# IRN-back-BNC.net
KiCad netlist of a schematic drawn in Altium Designer
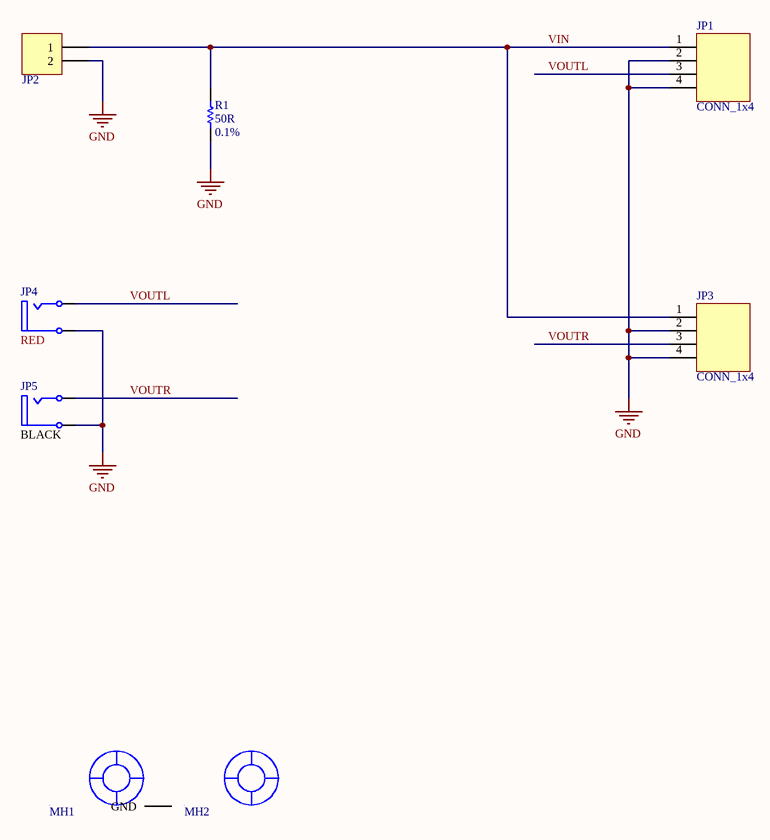
[diagram p0: IRN-back-BNC.SchDoc]

(export (version "E")
  (design (tool "Eeschema 10.0.6"))
  (components
    (comp (ref "JP1")
      (value "CONN_1x4")
      (footprint "CONN_HDR1X4-No3D")
      (description "Header, 4-Pin")
      (fields (field (name "MPN") "0470531000") (field (name "PUBLISHER") "Altium Limited"))
      (libsource (lib "micun") (part "CONN_MHDR_1x4"))
    )
    (comp (ref "JP2")
      (value "HDR1X2")
      (footprint "CONN_HDR1X2")
      (description "Header, 2-Pin")
      (libsource (lib "micun") (part "CONN_MHDR1X2"))
    )
    (comp (ref "JP3")
      (value "CONN_1x4")
      (footprint "CONN_HDR1X4-No3D")
      (description "Header, 4-Pin")
      (fields (field (name "MPN") "0470531000") (field (name "PUBLISHER") "Altium Limited"))
      (libsource (lib "micun") (part "CONN_MHDR_1x4"))
    )
    (comp (ref "JP4")
      (value "RED")
      (footprint "CONN_RCA-Lumberg-BTOR")
      (description "RCA panel-mount socket red, 1553 02 rot, Lumberg Connect GmbH")
      (fields (field (name "MPN") "BTOR 1 ROT") (field (name "Comment") "RCA RED"))
      (libsource (lib "micun") (part "CONN_RCA_LUMBERG_BTOR_1_RED"))
    )
    (comp (ref "JP5")
      (value "BLACK")
      (footprint "CONN_RCA-Lumberg-BTOR")
      (description "RCA panel-mount socket red, 1553 02 rot, Lumberg Connect GmbH")
      (fields (field (name "MPN") "BTOR 1 SCHWARZ") (field (name "Comment") "RCA BLACK"))
      (libsource (lib "micun") (part "CONN_RCA_LUMBERG_BTOR_1_BLACK"))
    )
    (comp (ref "MH1")
      (value "Mounting hole")
      (footprint "MECH_MHOLE_3.5-GND")
      (libsource (lib "micun") (part "MECH_MHOLE"))
    )
    (comp (ref "MH2")
      (value "Mounting hole")
      (footprint "MECH_MHOLE_3.5")
      (libsource (lib "") (part "MECH_MHOLE_1"))
    )
    (comp (ref "R1")
      (value "50R")
      (footprint "RESC0603(1608)_L")
      (description "0603 (1608 Metric) Chip Resistor")
      (fields (field (name "TOLERANCE") "0.1%") (field (name "Comment") "RES0603"))
      (libsource (lib "Altium Content Vault") (part "RES_3"))
    )
  )
  (nets
    (net (code "1") (name "/VIN") (class "Default")
      (node (ref "JP1") (pin "1") (pinfunction "1_1") (pintype "passive"))
      (node (ref "JP2") (pin "1") (pinfunction "1_1") (pintype "passive"))
      (node (ref "JP3") (pin "1") (pinfunction "1_1") (pintype "passive"))
      (node (ref "R1") (pin "1") (pinfunction "1_1") (pintype "passive"))
    )
    (net (code "2") (name "/VOUTL") (class "Default")
      (node (ref "JP1") (pin "3") (pinfunction "3_3") (pintype "passive"))
      (node (ref "JP4") (pin "1") (pinfunction "Signal_1") (pintype "passive"))
    )
    (net (code "3") (name "/VOUTR") (class "Default")
      (node (ref "JP3") (pin "3") (pinfunction "3_3") (pintype "passive"))
      (node (ref "JP5") (pin "1") (pinfunction "Signal_1") (pintype "passive"))
    )
    (net (code "4") (name "GND") (class "Default")
      (node (ref "JP1") (pin "2") (pinfunction "2_2") (pintype "passive"))
      (node (ref "JP1") (pin "4") (pinfunction "4_4") (pintype "passive"))
      (node (ref "JP2") (pin "2") (pinfunction "2_2") (pintype "passive"))
      (node (ref "JP3") (pin "2") (pinfunction "2_2") (pintype "passive"))
      (node (ref "JP3") (pin "4") (pinfunction "4_4") (pintype "passive"))
      (node (ref "JP4") (pin "2") (pinfunction "Ground_2") (pintype "power_in"))
      (node (ref "JP5") (pin "2") (pinfunction "Ground_2") (pintype "power_in"))
      (node (ref "R1") (pin "2") (pinfunction "2_2") (pintype "passive"))
    )
    (net (code "5") (name "unconnected-(MH1-GND-Pad0)") (class "Default")
      (node (ref "MH1") (pin "0") (pinfunction "GND_0") (pintype "power_in"))
    )
  )
)
